# Controller.net
KiCad netlist of a schematic drawn in EAGLE
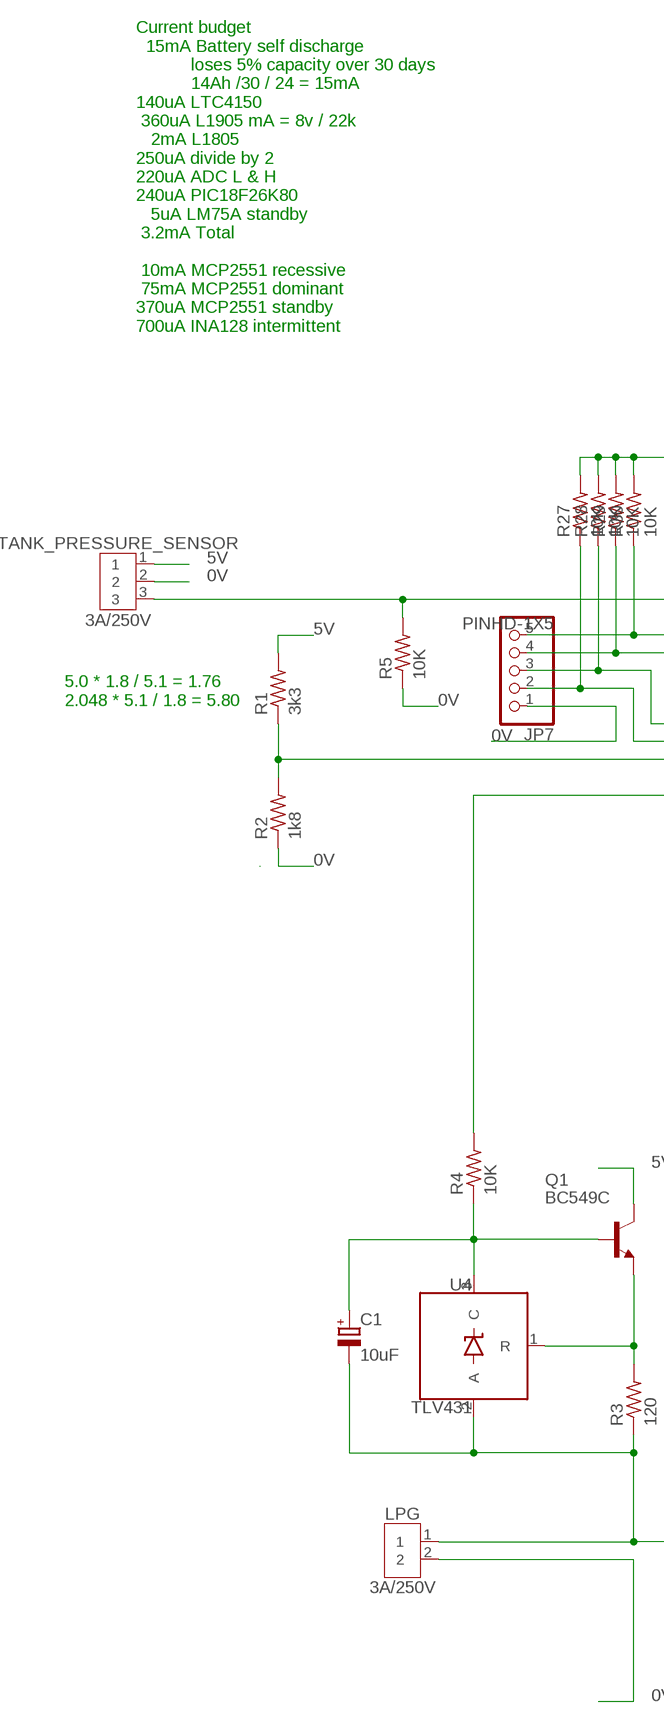
[diagram p0: schematic, sheet 1, part 1 of 2]
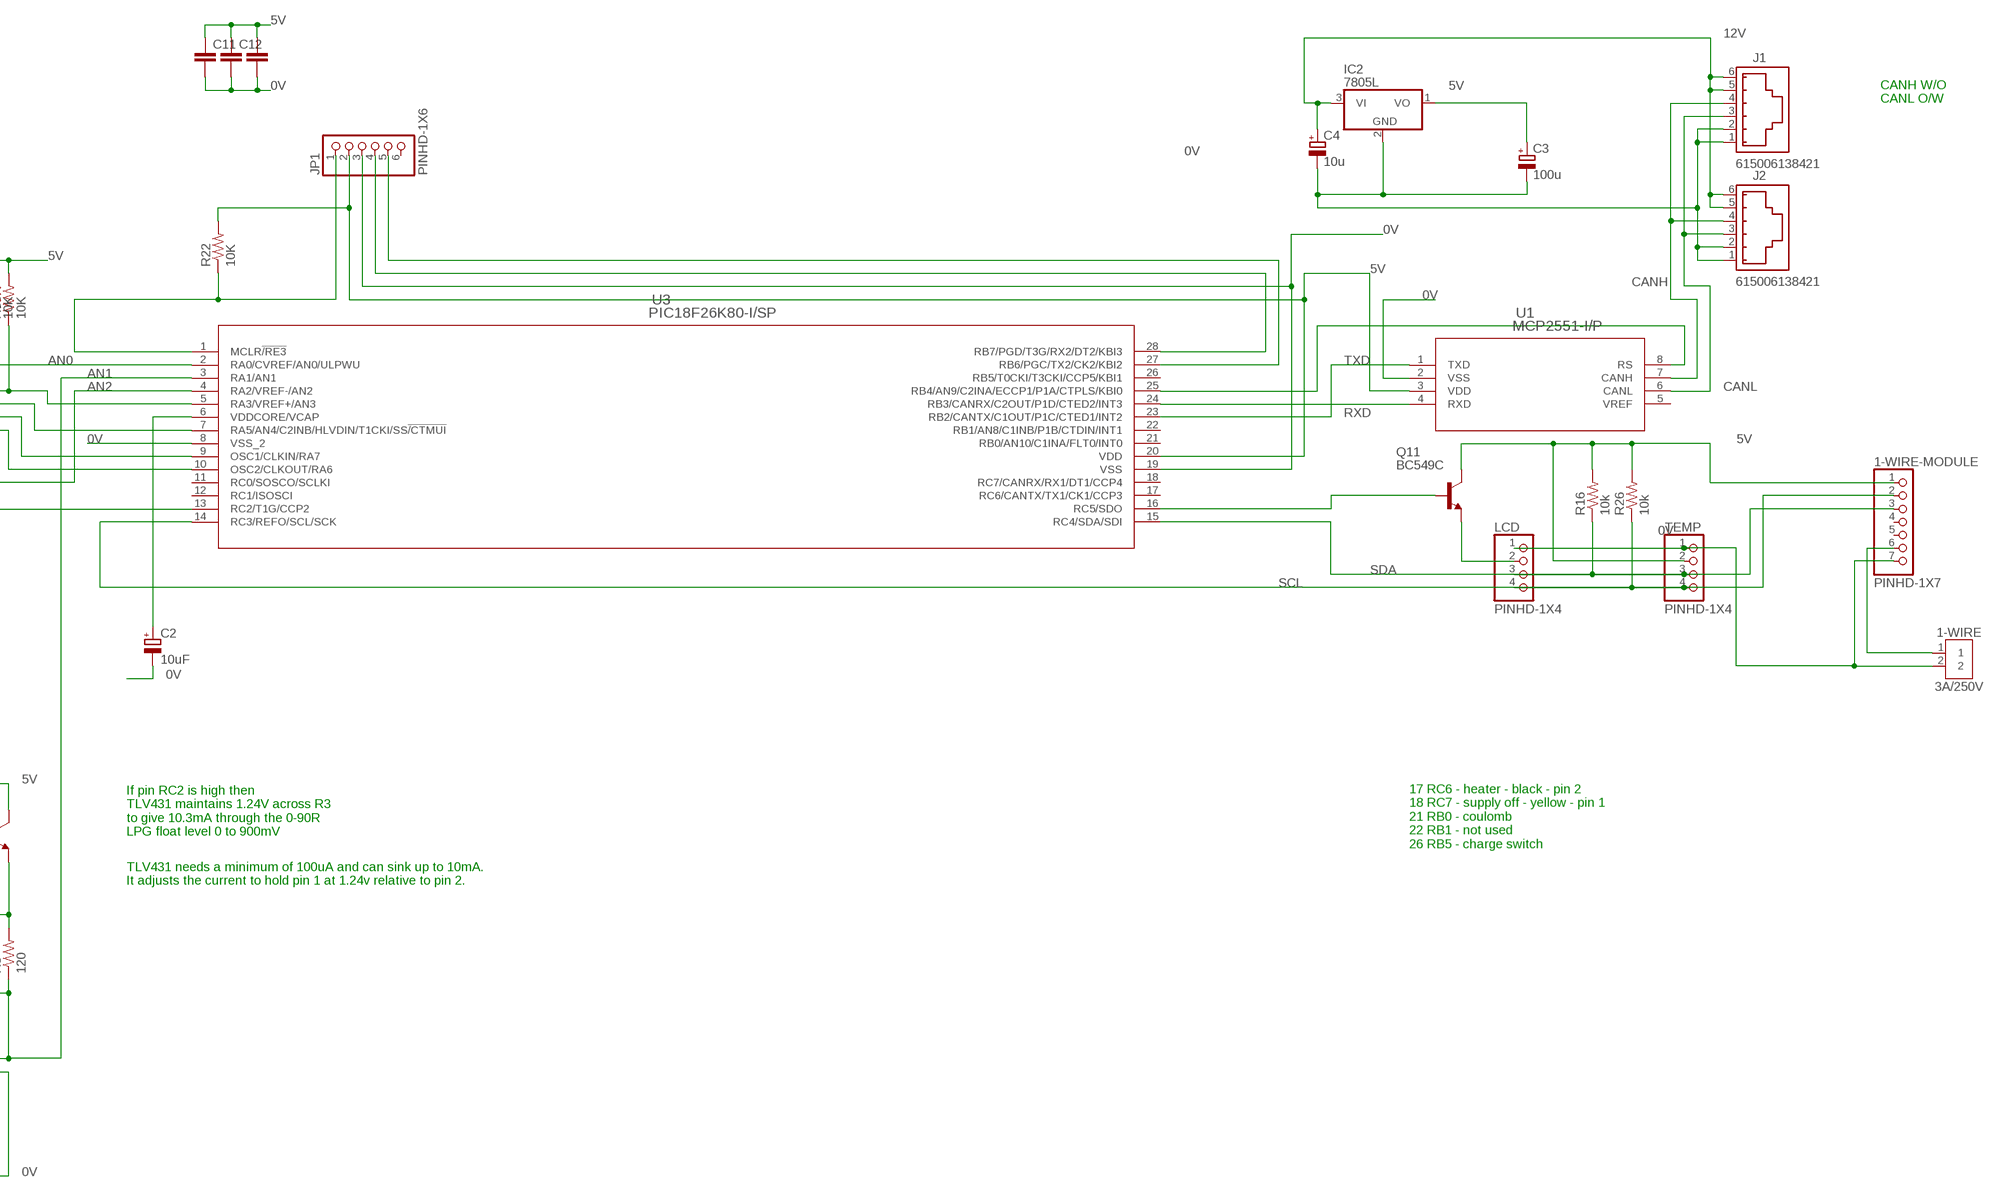
[diagram p1: schematic, sheet 1, part 2 of 2]

(export (version "E")
  (design (tool "Eeschema 10.0.6"))
  (components
    (comp (ref "1-WIRE")
      (value "3A/250V")
      (footprint "eagle-import:B2B-XH-A")
      (fields (field (name "MANUFACTURER") "JST (XH CONNECTOR)") (field (name "MPN") "B2B-XH-A"))
      (libsource (lib "eagle-import") (part "B2B-XH-A"))
    )
    (comp (ref "1-WIRE-MODULE")
      (value "PINHD-1X7")
      (footprint "eagle-import:1X07")
      (libsource (lib "eagle-import") (part "PINHD-1X7"))
    )
    (comp (ref "C1")
      (value "10uF")
      (footprint "eagle-import:E3,5-8")
      (libsource (lib "eagle-import") (part "CPOL-EUE3.5-8"))
    )
    (comp (ref "C2")
      (value "10uF")
      (footprint "eagle-import:E3,5-8")
      (libsource (lib "eagle-import") (part "CPOL-EUE3.5-8"))
    )
    (comp (ref "C3")
      (value "100u")
      (footprint "eagle-import:E3,5-8")
      (libsource (lib "eagle-import") (part "CPOL-EUE3.5-8"))
    )
    (comp (ref "C4")
      (value "10u")
      (footprint "eagle-import:E3,5-8")
      (libsource (lib "eagle-import") (part "CPOL-EUE3.5-8"))
    )
    (comp (ref "C7")
      (value "C2,5-3")
      (footprint "eagle-import:C2.5-3")
      (libsource (lib "eagle-import") (part "C2,5-3"))
    )
    (comp (ref "C11")
      (value "C2,5-3")
      (footprint "eagle-import:C2.5-3")
      (libsource (lib "eagle-import") (part "C2,5-3"))
    )
    (comp (ref "C12")
      (value "C2,5-3")
      (footprint "eagle-import:C2.5-3")
      (libsource (lib "eagle-import") (part "C2,5-3"))
    )
    (comp (ref "IC2")
      (value "7805L")
      (footprint "eagle-import:TO92")
      (libsource (lib "eagle-import") (part "78L05"))
    )
    (comp (ref "J1")
      (value "615006138421")
      (footprint "eagle-import:615006138421")
      (libsource (lib "eagle-import") (part "615006138421"))
    )
    (comp (ref "J2")
      (value "615006138421")
      (footprint "eagle-import:615006138421")
      (libsource (lib "eagle-import") (part "615006138421"))
    )
    (comp (ref "JP1")
      (value "PINHD-1X6")
      (footprint "eagle-import:1X06")
      (libsource (lib "eagle-import") (part "PINHD-1X6"))
    )
    (comp (ref "JP7")
      (value "PINHD-1X5")
      (footprint "eagle-import:1X05")
      (libsource (lib "eagle-import") (part "PINHD-1X5"))
    )
    (comp (ref "LCD")
      (value "PINHD-1X4")
      (footprint "eagle-import:1X04")
      (libsource (lib "eagle-import") (part "PINHD-1X4"))
    )
    (comp (ref "LPG")
      (value "3A/250V")
      (footprint "eagle-import:B2B-XH-A")
      (fields (field (name "MANUFACTURER") "JST (XH CONNECTOR)") (field (name "MPN") "B2B-XH-A"))
      (libsource (lib "eagle-import") (part "B2B-XH-A"))
    )
    (comp (ref "Q1")
      (value "BC549C")
      (footprint "eagle-import:TO92-EBC")
      (libsource (lib "eagle-import") (part "BC549C"))
    )
    (comp (ref "Q11")
      (value "BC549C")
      (footprint "eagle-import:TO92-EBC")
      (libsource (lib "eagle-import") (part "BC549C"))
    )
    (comp (ref "R1")
      (value "3k3")
      (footprint "eagle-import:0204_7")
      (libsource (lib "eagle-import") (part "RES_7"))
    )
    (comp (ref "R2")
      (value "1k8")
      (footprint "eagle-import:0204_7")
      (libsource (lib "eagle-import") (part "RES_7"))
    )
    (comp (ref "R3")
      (value "120")
      (footprint "eagle-import:0204_7")
      (libsource (lib "eagle-import") (part "RES_7"))
    )
    (comp (ref "R4")
      (value "10K")
      (footprint "eagle-import:0204_7")
      (libsource (lib "eagle-import") (part "RES_7"))
    )
    (comp (ref "R5")
      (value "10K")
      (footprint "eagle-import:0204_7")
      (libsource (lib "eagle-import") (part "RES_7"))
    )
    (comp (ref "R16")
      (value "10k")
      (footprint "eagle-import:0204_7")
      (libsource (lib "eagle-import") (part "RES_7"))
    )
    (comp (ref "R22")
      (value "10K")
      (footprint "eagle-import:0204_7")
      (libsource (lib "eagle-import") (part "RES_7"))
    )
    (comp (ref "R26")
      (value "10k")
      (footprint "eagle-import:0204_7")
      (libsource (lib "eagle-import") (part "RES_7"))
    )
    (comp (ref "R27")
      (value "10K")
      (footprint "eagle-import:0204_7-90")
      (libsource (lib "eagle-import") (part "RES_70204/7-90"))
    )
    (comp (ref "R28")
      (value "10K")
      (footprint "eagle-import:0204_7-90")
      (libsource (lib "eagle-import") (part "RES_70204/7-90"))
    )
    (comp (ref "R29")
      (value "10K")
      (footprint "eagle-import:0204_7-90")
      (libsource (lib "eagle-import") (part "RES_70204/7-90"))
    )
    (comp (ref "R30")
      (value "10K")
      (footprint "eagle-import:0204_7-90")
      (libsource (lib "eagle-import") (part "RES_70204/7-90"))
    )
    (comp (ref "TANK_PRESSURE_SENSOR")
      (value "3A/250V")
      (footprint "eagle-import:B3B-XH-A")
      (fields (field (name "MANUFACTURER") "JST (XH connector)") (field (name "MPN") "B3B-XH-A"))
      (libsource (lib "eagle-import") (part "B3B-XH-A"))
    )
    (comp (ref "TEMP")
      (value "PINHD-1X4")
      (footprint "eagle-import:1X04")
      (libsource (lib "eagle-import") (part "PINHD-1X4"))
    )
    (comp (ref "U1")
      (value "MCP2551-I/P")
      (footprint "eagle-import:PDIP8_300MC_MCH")
      (fields (field (name "COPYRIGHT") "Copyright (C) 2021 Ultra Librarian. All rights reserved."))
      (libsource (lib "eagle-import") (part "MCP2551-I/P"))
    )
    (comp (ref "U3")
      (value "PIC18F26K80-I/SP")
      (footprint "eagle-import:SPDIP28_300MC_MCH")
      (fields
        (field (name "MANUFACTURER_PART_NUMBER") "pic18f26k80-i/sp")
        (field (name "COPYRIGHT") "Copyright (C) 2021 Ultra Librarian. All rights reserved.")
      )
      (libsource (lib "eagle-import") (part "PIC18F26K80-I/SP"))
    )
    (comp (ref "U4")
      (value "TLV431")
      (footprint "eagle-import:TO92")
      (libsource (lib "eagle-import") (part "TLV431"))
    )
  )
  (nets
    (net (code "1") (name "/0V") (class "Default")
      (node (ref "1-WIRE") (pin "2") (pinfunction "2_2") (pintype "bidirectional"))
      (node (ref "1-WIRE-MODULE") (pin "7") (pinfunction "7_7") (pintype "passive"))
      (node (ref "C11") (pin "2") (pinfunction "2_2") (pintype "passive"))
      (node (ref "C12") (pin "2") (pinfunction "2_2") (pintype "passive"))
      (node (ref "C2") (pin "-") (pinfunction "-_-") (pintype "passive"))
      (node (ref "C3") (pin "-") (pinfunction "-_-") (pintype "passive"))
      (node (ref "C4") (pin "-") (pinfunction "-_-") (pintype "passive"))
      (node (ref "C7") (pin "2") (pinfunction "2_2") (pintype "passive"))
      (node (ref "IC2") (pin "2") (pinfunction "GND_2") (pintype "passive"))
      (node (ref "J1") (pin "1") (pinfunction "1_1") (pintype "passive"))
      (node (ref "J1") (pin "2") (pinfunction "2_2") (pintype "passive"))
      (node (ref "J2") (pin "1") (pinfunction "1_1") (pintype "passive"))
      (node (ref "J2") (pin "2") (pinfunction "2_2") (pintype "passive"))
      (node (ref "JP1") (pin "3") (pinfunction "3_3") (pintype "passive"))
      (node (ref "JP7") (pin "1") (pinfunction "1_1") (pintype "passive"))
      (node (ref "LCD") (pin "1") (pinfunction "1_1") (pintype "passive"))
      (node (ref "LPG") (pin "2") (pinfunction "2_2") (pintype "bidirectional"))
      (node (ref "R2") (pin "1") (pinfunction "1_1") (pintype "passive"))
      (node (ref "R5") (pin "1") (pinfunction "1_1") (pintype "passive"))
      (node (ref "TANK_PRESSURE_SENSOR") (pin "2") (pinfunction "2_2") (pintype "bidirectional"))
      (node (ref "TEMP") (pin "1") (pinfunction "1_1") (pintype "passive"))
      (node (ref "U1") (pin "2") (pinfunction "VSS_2") (pintype "passive"))
      (node (ref "U3") (pin "19") (pinfunction "VSS_19") (pintype "power_in"))
      (node (ref "U3") (pin "8") (pinfunction "VSS_2_8") (pintype "power_in"))
    )
    (net (code "2") (name "/5V") (class "Default")
      (node (ref "1-WIRE-MODULE") (pin "1") (pinfunction "1_1") (pintype "passive"))
      (node (ref "C11") (pin "1") (pinfunction "1_1") (pintype "passive"))
      (node (ref "C12") (pin "1") (pinfunction "1_1") (pintype "passive"))
      (node (ref "C3") (pin "+") (pinfunction "+_+") (pintype "passive"))
      (node (ref "C7") (pin "1") (pinfunction "1_1") (pintype "passive"))
      (node (ref "IC2") (pin "1") (pinfunction "VO_1") (pintype "passive"))
      (node (ref "JP1") (pin "2") (pinfunction "2_2") (pintype "passive"))
      (node (ref "Q1") (pin "C") (pinfunction "C_C") (pintype "passive"))
      (node (ref "Q11") (pin "C") (pinfunction "C_C") (pintype "passive"))
      (node (ref "R1") (pin "2") (pinfunction "2_2") (pintype "passive"))
      (node (ref "R16") (pin "2") (pinfunction "2_2") (pintype "passive"))
      (node (ref "R22") (pin "2") (pinfunction "2_2") (pintype "passive"))
      (node (ref "R26") (pin "2") (pinfunction "2_2") (pintype "passive"))
      (node (ref "R27") (pin "2") (pinfunction "2_2") (pintype "passive"))
      (node (ref "R28") (pin "2") (pinfunction "2_2") (pintype "passive"))
      (node (ref "R29") (pin "2") (pinfunction "2_2") (pintype "passive"))
      (node (ref "R30") (pin "2") (pinfunction "2_2") (pintype "passive"))
      (node (ref "TANK_PRESSURE_SENSOR") (pin "1") (pinfunction "1_1") (pintype "bidirectional"))
      (node (ref "TEMP") (pin "2") (pinfunction "2_2") (pintype "passive"))
      (node (ref "U1") (pin "3") (pinfunction "VDD_3") (pintype "passive"))
      (node (ref "U3") (pin "20") (pinfunction "VDD_20") (pintype "power_in"))
    )
    (net (code "3") (name "/12V") (class "Default")
      (node (ref "C4") (pin "+") (pinfunction "+_+") (pintype "passive"))
      (node (ref "IC2") (pin "3") (pinfunction "VI_3") (pintype "input"))
      (node (ref "J1") (pin "5") (pinfunction "5_5") (pintype "passive"))
      (node (ref "J1") (pin "6") (pinfunction "6_6") (pintype "passive"))
      (node (ref "J2") (pin "5") (pinfunction "5_5") (pintype "passive"))
      (node (ref "J2") (pin "6") (pinfunction "6_6") (pintype "passive"))
    )
    (net (code "4") (name "/AN0") (class "Default")
      (node (ref "R5") (pin "2") (pinfunction "2_2") (pintype "passive"))
      (node (ref "TANK_PRESSURE_SENSOR") (pin "3") (pinfunction "3_3") (pintype "bidirectional"))
      (node (ref "U3") (pin "2") (pinfunction "RA0/CVREF/AN0/ULPWU_2") (pintype "bidirectional"))
    )
    (net (code "5") (name "/AN1") (class "Default")
      (node (ref "C1") (pin "-") (pinfunction "-_-") (pintype "passive"))
      (node (ref "LPG") (pin "1") (pinfunction "1_1") (pintype "bidirectional"))
      (node (ref "R3") (pin "1") (pinfunction "1_1") (pintype "passive"))
      (node (ref "U3") (pin "3") (pinfunction "RA1/AN1_3") (pintype "bidirectional"))
      (node (ref "U4") (pin "2") (pinfunction "A_2") (pintype "bidirectional"))
    )
    (net (code "6") (name "/AN2") (class "Default")
      (node (ref "R1") (pin "1") (pinfunction "1_1") (pintype "passive"))
      (node (ref "R2") (pin "2") (pinfunction "2_2") (pintype "passive"))
      (node (ref "U3") (pin "4") (pinfunction "RA2/VREF-/AN2_4") (pintype "bidirectional"))
    )
    (net (code "7") (name "/CANH") (class "Default")
      (node (ref "J1") (pin "4") (pinfunction "4_4") (pintype "passive"))
      (node (ref "J2") (pin "4") (pinfunction "4_4") (pintype "passive"))
      (node (ref "U1") (pin "7") (pinfunction "CANH_7") (pintype "passive"))
    )
    (net (code "8") (name "/CANL") (class "Default")
      (node (ref "J1") (pin "3") (pinfunction "3_3") (pintype "passive"))
      (node (ref "J2") (pin "3") (pinfunction "3_3") (pintype "passive"))
      (node (ref "U1") (pin "6") (pinfunction "CANL_6") (pintype "passive"))
    )
    (net (code "9") (name "/RXD") (class "Default")
      (node (ref "U1") (pin "4") (pinfunction "RXD_4") (pintype "passive"))
      (node (ref "U3") (pin "24") (pinfunction "RB3/CANRX/C2OUT/P1D/CTED2/INT3_24") (pintype "bidirectional"))
    )
    (net (code "10") (name "/SCL") (class "Default")
      (node (ref "1-WIRE-MODULE") (pin "2") (pinfunction "2_2") (pintype "passive"))
      (node (ref "LCD") (pin "4") (pinfunction "4_4") (pintype "passive"))
      (node (ref "R26") (pin "1") (pinfunction "1_1") (pintype "passive"))
      (node (ref "TEMP") (pin "4") (pinfunction "4_4") (pintype "passive"))
      (node (ref "U3") (pin "14") (pinfunction "RC3/REFO/SCL/SCK_14") (pintype "bidirectional"))
    )
    (net (code "11") (name "/SDA") (class "Default")
      (node (ref "1-WIRE-MODULE") (pin "3") (pinfunction "3_3") (pintype "passive"))
      (node (ref "LCD") (pin "3") (pinfunction "3_3") (pintype "passive"))
      (node (ref "R16") (pin "1") (pinfunction "1_1") (pintype "passive"))
      (node (ref "TEMP") (pin "3") (pinfunction "3_3") (pintype "passive"))
      (node (ref "U3") (pin "15") (pinfunction "RC4/SDA/SDI_15") (pintype "bidirectional"))
    )
    (net (code "12") (name "/TXD") (class "Default")
      (node (ref "U1") (pin "1") (pinfunction "TXD_1") (pintype "passive"))
      (node (ref "U3") (pin "23") (pinfunction "RB2/CANTX/C1OUT/P1C/CTED1/INT2_23") (pintype "bidirectional"))
    )
    (net (code "13") (name "Net-(1-WIRE-MODULE-Pad6)") (class "Default")
      (node (ref "1-WIRE") (pin "1") (pinfunction "1_1") (pintype "bidirectional"))
      (node (ref "1-WIRE-MODULE") (pin "6") (pinfunction "6_6") (pintype "passive"))
    )
    (net (code "14") (name "Net-(LCD-Pad2)") (class "Default")
      (node (ref "LCD") (pin "2") (pinfunction "2_2") (pintype "passive"))
      (node (ref "Q11") (pin "E") (pinfunction "E_E") (pintype "passive"))
    )
    (net (code "15") (name "Net-(U1-RS)") (class "Default")
      (node (ref "U1") (pin "8") (pinfunction "RS_8") (pintype "passive"))
      (node (ref "U3") (pin "25") (pinfunction "RB4/AN9/C2INA/ECCP1/P1A/CTPLS/KBI0_25") (pintype "bidirectional"))
    )
    (net (code "16") (name "Net-(U3-MCLR~{{slash}RE3})") (class "Default")
      (node (ref "JP1") (pin "1") (pinfunction "1_1") (pintype "passive"))
      (node (ref "R22") (pin "1") (pinfunction "1_1") (pintype "passive"))
      (node (ref "U3") (pin "1") (pinfunction "MCLR~{/RE3}_1") (pintype "bidirectional"))
    )
    (net (code "17") (name "Net-(U3-OSC1{slash}CLKIN{slash}RA7)") (class "Default")
      (node (ref "JP7") (pin "3") (pinfunction "3_3") (pintype "passive"))
      (node (ref "R28") (pin "1") (pinfunction "1_1") (pintype "passive"))
      (node (ref "U3") (pin "9") (pinfunction "OSC1/CLKIN/RA7_9") (pintype "bidirectional"))
    )
    (net (code "18") (name "Net-(U3-OSC2{slash}CLKOUT{slash}RA6)") (class "Default")
      (node (ref "JP7") (pin "2") (pinfunction "2_2") (pintype "passive"))
      (node (ref "R27") (pin "1") (pinfunction "1_1") (pintype "passive"))
      (node (ref "U3") (pin "10") (pinfunction "OSC2/CLKOUT/RA6_10") (pintype "bidirectional"))
    )
    (net (code "19") (name "Net-(U3-RA3{slash}VREF+{slash}AN3)") (class "Default")
      (node (ref "JP7") (pin "5") (pinfunction "5_5") (pintype "passive"))
      (node (ref "R30") (pin "1") (pinfunction "1_1") (pintype "passive"))
      (node (ref "U3") (pin "5") (pinfunction "RA3/VREF+/AN3_5") (pintype "bidirectional"))
    )
    (net (code "20") (name "Net-(U3-RA5{slash}AN4{slash}C2INB{slash}HLVDIN{slash}T1CKI{slash}SS~{{slash}CTMUI})") (class "Default")
      (node (ref "JP7") (pin "4") (pinfunction "4_4") (pintype "passive"))
      (node (ref "R29") (pin "1") (pinfunction "1_1") (pintype "passive"))
      (node (ref "U3") (pin "7") (pinfunction "RA5/AN4/C2INB/HLVDIN/T1CKI/SS~{/CTMUI}_7") (pintype "bidirectional"))
    )
    (net (code "21") (name "Net-(U3-RB6{slash}PGC{slash}TX2{slash}CK2{slash}KBI2)") (class "Default")
      (node (ref "JP1") (pin "5") (pinfunction "5_5") (pintype "passive"))
      (node (ref "U3") (pin "27") (pinfunction "RB6/PGC/TX2/CK2/KBI2_27") (pintype "bidirectional"))
    )
    (net (code "22") (name "Net-(U3-RB7{slash}PGD{slash}T3G{slash}RX2{slash}DT2{slash}KBI3)") (class "Default")
      (node (ref "JP1") (pin "4") (pinfunction "4_4") (pintype "passive"))
      (node (ref "U3") (pin "28") (pinfunction "RB7/PGD/T3G/RX2/DT2/KBI3_28") (pintype "bidirectional"))
    )
    (net (code "23") (name "Net-(U3-RC2{slash}T1G{slash}CCP2)") (class "Default")
      (node (ref "R4") (pin "2") (pinfunction "2_2") (pintype "passive"))
      (node (ref "U3") (pin "13") (pinfunction "RC2/T1G/CCP2_13") (pintype "bidirectional"))
    )
    (net (code "24") (name "Net-(U3-RC5{slash}SDO)") (class "Default")
      (node (ref "Q11") (pin "B") (pinfunction "B_B") (pintype "passive"))
      (node (ref "U3") (pin "16") (pinfunction "RC5/SDO_16") (pintype "bidirectional"))
    )
    (net (code "25") (name "Net-(U3-VDDCORE{slash}VCAP)") (class "Default")
      (node (ref "C2") (pin "+") (pinfunction "+_+") (pintype "passive"))
      (node (ref "U3") (pin "6") (pinfunction "VDDCORE/VCAP_6") (pintype "power_in"))
    )
    (net (code "26") (name "Net-(U4-C)") (class "Default")
      (node (ref "C1") (pin "+") (pinfunction "+_+") (pintype "passive"))
      (node (ref "Q1") (pin "B") (pinfunction "B_B") (pintype "passive"))
      (node (ref "R4") (pin "1") (pinfunction "1_1") (pintype "passive"))
      (node (ref "U4") (pin "3") (pinfunction "C_3") (pintype "bidirectional"))
    )
    (net (code "27") (name "Net-(U4-R)") (class "Default")
      (node (ref "Q1") (pin "E") (pinfunction "E_E") (pintype "passive"))
      (node (ref "R3") (pin "2") (pinfunction "2_2") (pintype "passive"))
      (node (ref "U4") (pin "1") (pinfunction "R_1") (pintype "bidirectional"))
    )
    (net (code "28") (name "unconnected-(1-WIRE-MODULE-Pad4)") (class "Default")
      (node (ref "1-WIRE-MODULE") (pin "4") (pinfunction "4_4") (pintype "passive"))
    )
    (net (code "29") (name "unconnected-(1-WIRE-MODULE-Pad5)") (class "Default")
      (node (ref "1-WIRE-MODULE") (pin "5") (pinfunction "5_5") (pintype "passive"))
    )
    (net (code "30") (name "unconnected-(JP1-Pad6)") (class "Default")
      (node (ref "JP1") (pin "6") (pinfunction "6_6") (pintype "passive"))
    )
    (net (code "31") (name "unconnected-(U1-VREF-Pad5)") (class "Default")
      (node (ref "U1") (pin "5") (pinfunction "VREF_5") (pintype "passive"))
    )
    (net (code "32") (name "unconnected-(U3-RB0{slash}AN10{slash}C1INA{slash}FLT0{slash}INT0-Pad21)") (class "Default")
      (node (ref "U3") (pin "21") (pinfunction "RB0/AN10/C1INA/FLT0/INT0_21") (pintype "bidirectional"))
    )
    (net (code "33") (name "unconnected-(U3-RB1{slash}AN8{slash}C1INB{slash}P1B{slash}CTDIN{slash}INT1-Pad22)") (class "Default")
      (node (ref "U3") (pin "22") (pinfunction "RB1/AN8/C1INB/P1B/CTDIN/INT1_22") (pintype "bidirectional"))
    )
    (net (code "34") (name "unconnected-(U3-RB5{slash}T0CKI{slash}T3CKI{slash}CCP5{slash}KBI1-Pad26)") (class "Default")
      (node (ref "U3") (pin "26") (pinfunction "RB5/T0CKI/T3CKI/CCP5/KBI1_26") (pintype "bidirectional"))
    )
    (net (code "35") (name "unconnected-(U3-RC0{slash}SOSCO{slash}SCLKI-Pad11)") (class "Default")
      (node (ref "U3") (pin "11") (pinfunction "RC0/SOSCO/SCLKI_11") (pintype "bidirectional"))
    )
    (net (code "36") (name "unconnected-(U3-RC1{slash}ISOSCI-Pad12)") (class "Default")
      (node (ref "U3") (pin "12") (pinfunction "RC1/ISOSCI_12") (pintype "bidirectional"))
    )
    (net (code "37") (name "unconnected-(U3-RC6{slash}CANTX{slash}TX1{slash}CK1{slash}CCP3-Pad17)") (class "Default")
      (node (ref "U3") (pin "17") (pinfunction "RC6/CANTX/TX1/CK1/CCP3_17") (pintype "bidirectional"))
    )
    (net (code "38") (name "unconnected-(U3-RC7{slash}CANRX{slash}RX1{slash}DT1{slash}CCP4-Pad18)") (class "Default")
      (node (ref "U3") (pin "18") (pinfunction "RC7/CANRX/RX1/DT1/CCP4_18") (pintype "bidirectional"))
    )
  )
)
